# S202D.net
KiCad netlist of a schematic drawn in EAGLE
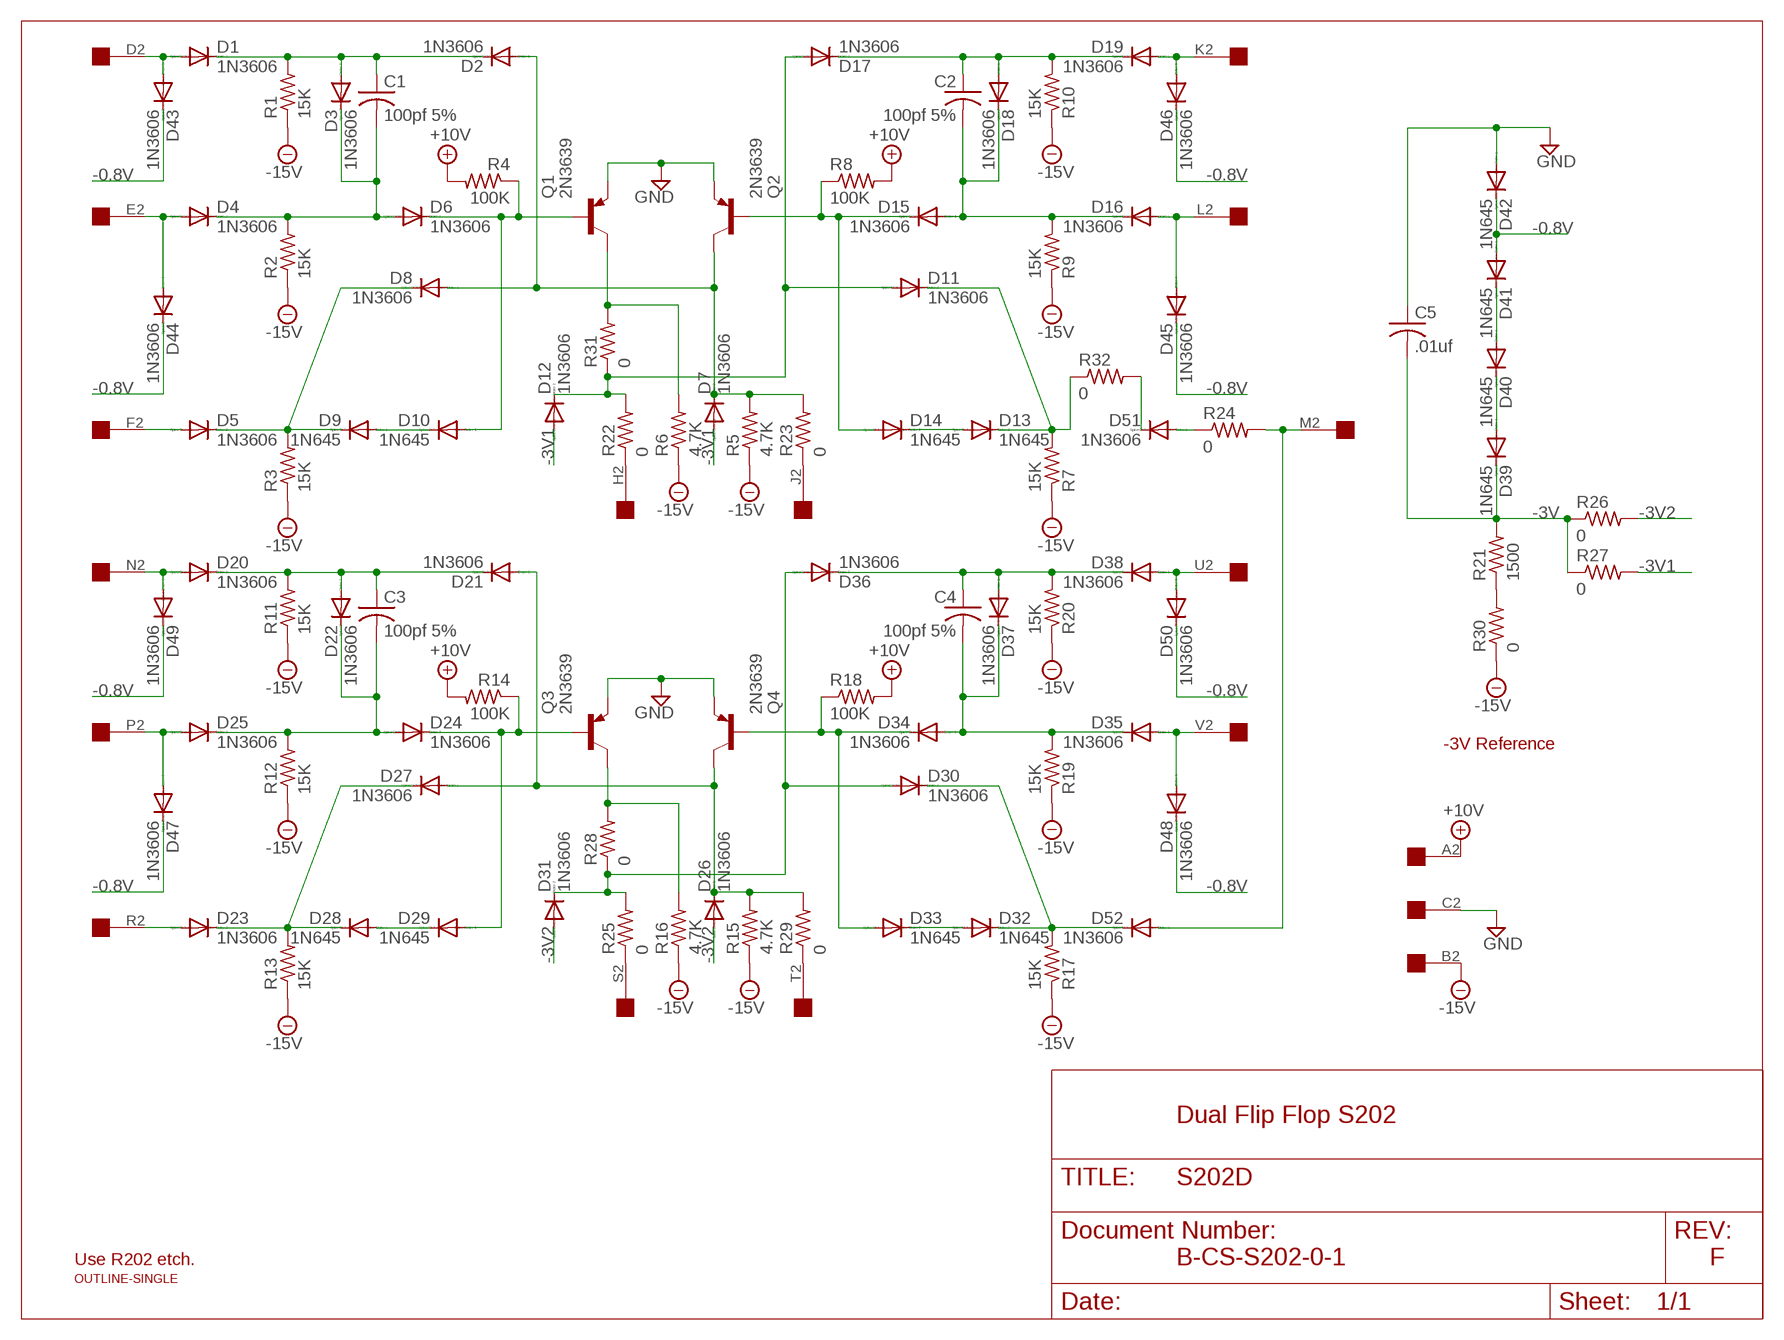
[diagram p0: schematic, sheet 1]

(export (version "E")
  (design (tool "Eeschema 10.0.6"))
  (components
    (comp (ref "C1")
      (value "100pf 5%")
      (footprint "eagle-import:C050-025X075")
      (libsource (lib "eagle-import") (part "C-US050-025X075"))
    )
    (comp (ref "C2")
      (value "100pf 5%")
      (footprint "eagle-import:C050-025X075")
      (libsource (lib "eagle-import") (part "C-US050-025X075"))
    )
    (comp (ref "C3")
      (value "100pf 5%")
      (footprint "eagle-import:C050-025X075")
      (libsource (lib "eagle-import") (part "C-US050-025X075"))
    )
    (comp (ref "C4")
      (value "100pf 5%")
      (footprint "eagle-import:C050-025X075")
      (libsource (lib "eagle-import") (part "C-US050-025X075"))
    )
    (comp (ref "C5")
      (value ".01uf")
      (footprint "eagle-import:C050-025X075")
      (libsource (lib "eagle-import") (part "C-US050-025X075"))
    )
    (comp (ref "D1")
      (value "1N3606")
      (footprint "eagle-import:DO35-10")
      (libsource (lib "eagle-import") (part "1N4148DO35-10"))
    )
    (comp (ref "D2")
      (value "1N3606")
      (footprint "eagle-import:DO35-10")
      (libsource (lib "eagle-import") (part "1N4148DO35-10"))
    )
    (comp (ref "D3")
      (value "1N3606")
      (footprint "eagle-import:DO35-10")
      (libsource (lib "eagle-import") (part "1N4148DO35-10"))
    )
    (comp (ref "D4")
      (value "1N3606")
      (footprint "eagle-import:DO35-10")
      (libsource (lib "eagle-import") (part "1N4148DO35-10"))
    )
    (comp (ref "D5")
      (value "1N3606")
      (footprint "eagle-import:DO35-10")
      (libsource (lib "eagle-import") (part "1N4148DO35-10"))
    )
    (comp (ref "D6")
      (value "1N3606")
      (footprint "eagle-import:DO35-10")
      (libsource (lib "eagle-import") (part "1N4148DO35-10"))
    )
    (comp (ref "D7")
      (value "1N3606")
      (footprint "eagle-import:DO35-10")
      (libsource (lib "eagle-import") (part "1N4148DO35-10"))
    )
    (comp (ref "D8")
      (value "1N3606")
      (footprint "eagle-import:DO35-10")
      (libsource (lib "eagle-import") (part "1N4148DO35-10"))
    )
    (comp (ref "D9")
      (value "1N645")
      (footprint "eagle-import:DO35-10")
      (libsource (lib "eagle-import") (part "1N4148DO35-10"))
    )
    (comp (ref "D10")
      (value "1N645")
      (footprint "eagle-import:DO35-10")
      (libsource (lib "eagle-import") (part "1N4148DO35-10"))
    )
    (comp (ref "D11")
      (value "1N3606")
      (footprint "eagle-import:DO35-10")
      (libsource (lib "eagle-import") (part "1N4148DO35-10"))
    )
    (comp (ref "D12")
      (value "1N3606")
      (footprint "eagle-import:DO35-10")
      (libsource (lib "eagle-import") (part "1N4148DO35-10"))
    )
    (comp (ref "D13")
      (value "1N645")
      (footprint "eagle-import:DO35-10")
      (libsource (lib "eagle-import") (part "1N4148DO35-10"))
    )
    (comp (ref "D14")
      (value "1N645")
      (footprint "eagle-import:DO35-10")
      (libsource (lib "eagle-import") (part "1N4148DO35-10"))
    )
    (comp (ref "D15")
      (value "1N3606")
      (footprint "eagle-import:DO35-10")
      (libsource (lib "eagle-import") (part "1N4148DO35-10"))
    )
    (comp (ref "D16")
      (value "1N3606")
      (footprint "eagle-import:DO35-10")
      (libsource (lib "eagle-import") (part "1N4148DO35-10"))
    )
    (comp (ref "D17")
      (value "1N3606")
      (footprint "eagle-import:DO35-10")
      (libsource (lib "eagle-import") (part "1N4148DO35-10"))
    )
    (comp (ref "D18")
      (value "1N3606")
      (footprint "eagle-import:DO35-10")
      (libsource (lib "eagle-import") (part "1N4148DO35-10"))
    )
    (comp (ref "D19")
      (value "1N3606")
      (footprint "eagle-import:DO35-10")
      (libsource (lib "eagle-import") (part "1N4148DO35-10"))
    )
    (comp (ref "D20")
      (value "1N3606")
      (footprint "eagle-import:DO35-10")
      (libsource (lib "eagle-import") (part "1N4148DO35-10"))
    )
    (comp (ref "D21")
      (value "1N3606")
      (footprint "eagle-import:DO35-10")
      (libsource (lib "eagle-import") (part "1N4148DO35-10"))
    )
    (comp (ref "D22")
      (value "1N3606")
      (footprint "eagle-import:DO35-10")
      (libsource (lib "eagle-import") (part "1N4148DO35-10"))
    )
    (comp (ref "D23")
      (value "1N3606")
      (footprint "eagle-import:DO35-10")
      (libsource (lib "eagle-import") (part "1N4148DO35-10"))
    )
    (comp (ref "D24")
      (value "1N3606")
      (footprint "eagle-import:DO35-10")
      (libsource (lib "eagle-import") (part "1N4148DO35-10"))
    )
    (comp (ref "D25")
      (value "1N3606")
      (footprint "eagle-import:DO35-10")
      (libsource (lib "eagle-import") (part "1N4148DO35-10"))
    )
    (comp (ref "D26")
      (value "1N3606")
      (footprint "eagle-import:DO35-10")
      (libsource (lib "eagle-import") (part "1N4148DO35-10"))
    )
    (comp (ref "D27")
      (value "1N3606")
      (footprint "eagle-import:DO35-10")
      (libsource (lib "eagle-import") (part "1N4148DO35-10"))
    )
    (comp (ref "D28")
      (value "1N645")
      (footprint "eagle-import:DO35-10")
      (libsource (lib "eagle-import") (part "1N4148DO35-10"))
    )
    (comp (ref "D29")
      (value "1N645")
      (footprint "eagle-import:DO35-10")
      (libsource (lib "eagle-import") (part "1N4148DO35-10"))
    )
    (comp (ref "D30")
      (value "1N3606")
      (footprint "eagle-import:DO35-10")
      (libsource (lib "eagle-import") (part "1N4148DO35-10"))
    )
    (comp (ref "D31")
      (value "1N3606")
      (footprint "eagle-import:DO35-10")
      (libsource (lib "eagle-import") (part "1N4148DO35-10"))
    )
    (comp (ref "D32")
      (value "1N645")
      (footprint "eagle-import:DO35-10")
      (libsource (lib "eagle-import") (part "1N4148DO35-10"))
    )
    (comp (ref "D33")
      (value "1N645")
      (footprint "eagle-import:DO35-10")
      (libsource (lib "eagle-import") (part "1N4148DO35-10"))
    )
    (comp (ref "D34")
      (value "1N3606")
      (footprint "eagle-import:DO35-10")
      (libsource (lib "eagle-import") (part "1N4148DO35-10"))
    )
    (comp (ref "D35")
      (value "1N3606")
      (footprint "eagle-import:DO35-10")
      (libsource (lib "eagle-import") (part "1N4148DO35-10"))
    )
    (comp (ref "D36")
      (value "1N3606")
      (footprint "eagle-import:DO35-10")
      (libsource (lib "eagle-import") (part "1N4148DO35-10"))
    )
    (comp (ref "D37")
      (value "1N3606")
      (footprint "eagle-import:DO35-10")
      (libsource (lib "eagle-import") (part "1N4148DO35-10"))
    )
    (comp (ref "D38")
      (value "1N3606")
      (footprint "eagle-import:DO35-10")
      (libsource (lib "eagle-import") (part "1N4148DO35-10"))
    )
    (comp (ref "D39")
      (value "1N645")
      (footprint "eagle-import:DO35-10")
      (libsource (lib "eagle-import") (part "1N4148DO35-10"))
    )
    (comp (ref "D40")
      (value "1N645")
      (footprint "eagle-import:DO35-10")
      (libsource (lib "eagle-import") (part "1N4148DO35-10"))
    )
    (comp (ref "D41")
      (value "1N645")
      (footprint "eagle-import:DO35-10")
      (libsource (lib "eagle-import") (part "1N4148DO35-10"))
    )
    (comp (ref "D42")
      (value "1N645")
      (footprint "eagle-import:DO35-10")
      (libsource (lib "eagle-import") (part "1N4148DO35-10"))
    )
    (comp (ref "D43")
      (value "1N3606")
      (footprint "eagle-import:DO35-10")
      (libsource (lib "eagle-import") (part "1N4148DO35-10"))
    )
    (comp (ref "D44")
      (value "1N3606")
      (footprint "eagle-import:DO35-10")
      (libsource (lib "eagle-import") (part "1N4148DO35-10"))
    )
    (comp (ref "D45")
      (value "1N3606")
      (footprint "eagle-import:DO35-10")
      (libsource (lib "eagle-import") (part "1N4148DO35-10"))
    )
    (comp (ref "D46")
      (value "1N3606")
      (footprint "eagle-import:DO35-10")
      (libsource (lib "eagle-import") (part "1N4148DO35-10"))
    )
    (comp (ref "D47")
      (value "1N3606")
      (footprint "eagle-import:DO35-10")
      (libsource (lib "eagle-import") (part "1N4148DO35-10"))
    )
    (comp (ref "D48")
      (value "1N3606")
      (footprint "eagle-import:DO35-10")
      (libsource (lib "eagle-import") (part "1N4148DO35-10"))
    )
    (comp (ref "D49")
      (value "1N3606")
      (footprint "eagle-import:DO35-10")
      (libsource (lib "eagle-import") (part "1N4148DO35-10"))
    )
    (comp (ref "D50")
      (value "1N3606")
      (footprint "eagle-import:DO35-10")
      (libsource (lib "eagle-import") (part "1N4148DO35-10"))
    )
    (comp (ref "D51")
      (value "1N3606")
      (footprint "eagle-import:DO35-10")
      (libsource (lib "eagle-import") (part "1N4148DO35-10"))
    )
    (comp (ref "D52")
      (value "1N3606")
      (footprint "eagle-import:DO35-10")
      (libsource (lib "eagle-import") (part "1N4148DO35-10"))
    )
    (comp (ref "Q1")
      (value "2N3639")
      (footprint "eagle-import:TO39")
      (libsource (lib "eagle-import") (part "2N3637"))
    )
    (comp (ref "Q2")
      (value "2N3639")
      (footprint "eagle-import:TO39")
      (libsource (lib "eagle-import") (part "2N3637"))
    )
    (comp (ref "Q3")
      (value "2N3639")
      (footprint "eagle-import:TO39")
      (libsource (lib "eagle-import") (part "2N3637"))
    )
    (comp (ref "Q4")
      (value "2N3639")
      (footprint "eagle-import:TO39")
      (libsource (lib "eagle-import") (part "2N3637"))
    )
    (comp (ref "R1")
      (value "15K")
      (footprint "eagle-import:0207_10")
      (libsource (lib "eagle-import") (part "R-US_0207/10"))
    )
    (comp (ref "R2")
      (value "15K")
      (footprint "eagle-import:0207_10")
      (libsource (lib "eagle-import") (part "R-US_0207/10"))
    )
    (comp (ref "R3")
      (value "15K")
      (footprint "eagle-import:0207_10")
      (libsource (lib "eagle-import") (part "R-US_0207/10"))
    )
    (comp (ref "R4")
      (value "100K")
      (footprint "eagle-import:0207_10")
      (libsource (lib "eagle-import") (part "R-US_0207/10"))
    )
    (comp (ref "R5")
      (value "4.7K")
      (footprint "eagle-import:0207_10")
      (libsource (lib "eagle-import") (part "R-US_0207/10"))
    )
    (comp (ref "R6")
      (value "4.7K")
      (footprint "eagle-import:0207_10")
      (libsource (lib "eagle-import") (part "R-US_0207/10"))
    )
    (comp (ref "R7")
      (value "15K")
      (footprint "eagle-import:0207_10")
      (libsource (lib "eagle-import") (part "R-US_0207/10"))
    )
    (comp (ref "R8")
      (value "100K")
      (footprint "eagle-import:0207_10")
      (libsource (lib "eagle-import") (part "R-US_0207/10"))
    )
    (comp (ref "R9")
      (value "15K")
      (footprint "eagle-import:0207_10")
      (libsource (lib "eagle-import") (part "R-US_0207/10"))
    )
    (comp (ref "R10")
      (value "15K")
      (footprint "eagle-import:0207_10")
      (libsource (lib "eagle-import") (part "R-US_0207/10"))
    )
    (comp (ref "R11")
      (value "15K")
      (footprint "eagle-import:0207_10")
      (libsource (lib "eagle-import") (part "R-US_0207/10"))
    )
    (comp (ref "R12")
      (value "15K")
      (footprint "eagle-import:0207_10")
      (libsource (lib "eagle-import") (part "R-US_0207/10"))
    )
    (comp (ref "R13")
      (value "15K")
      (footprint "eagle-import:0207_10")
      (libsource (lib "eagle-import") (part "R-US_0207/10"))
    )
    (comp (ref "R14")
      (value "100K")
      (footprint "eagle-import:0207_10")
      (libsource (lib "eagle-import") (part "R-US_0207/10"))
    )
    (comp (ref "R15")
      (value "4.7K")
      (footprint "eagle-import:0207_10")
      (libsource (lib "eagle-import") (part "R-US_0207/10"))
    )
    (comp (ref "R16")
      (value "4.7K")
      (footprint "eagle-import:0207_10")
      (libsource (lib "eagle-import") (part "R-US_0207/10"))
    )
    (comp (ref "R17")
      (value "15K")
      (footprint "eagle-import:0207_10")
      (libsource (lib "eagle-import") (part "R-US_0207/10"))
    )
    (comp (ref "R18")
      (value "100K")
      (footprint "eagle-import:0207_10")
      (libsource (lib "eagle-import") (part "R-US_0207/10"))
    )
    (comp (ref "R19")
      (value "15K")
      (footprint "eagle-import:0207_10")
      (libsource (lib "eagle-import") (part "R-US_0207/10"))
    )
    (comp (ref "R20")
      (value "15K")
      (footprint "eagle-import:0207_10")
      (libsource (lib "eagle-import") (part "R-US_0207/10"))
    )
    (comp (ref "R21")
      (value "1500")
      (footprint "eagle-import:0207_10")
      (libsource (lib "eagle-import") (part "R-US_0207/10"))
    )
    (comp (ref "R22")
      (value "0")
      (footprint "eagle-import:0207_10")
      (libsource (lib "eagle-import") (part "R-US_0207/10"))
    )
    (comp (ref "R23")
      (value "0")
      (footprint "eagle-import:0207_10")
      (libsource (lib "eagle-import") (part "R-US_0207/10"))
    )
    (comp (ref "R24")
      (value "0")
      (footprint "eagle-import:0207_10")
      (libsource (lib "eagle-import") (part "R-US_0207/10"))
    )
    (comp (ref "R25")
      (value "0")
      (footprint "eagle-import:0207_10")
      (libsource (lib "eagle-import") (part "R-US_0207/10"))
    )
    (comp (ref "R26")
      (value "0")
      (footprint "eagle-import:0207_10")
      (libsource (lib "eagle-import") (part "R-US_0207/10"))
    )
    (comp (ref "R27")
      (value "0")
      (footprint "eagle-import:0207_10")
      (libsource (lib "eagle-import") (part "R-US_0207/10"))
    )
    (comp (ref "R28")
      (value "0")
      (footprint "eagle-import:0207_10")
      (libsource (lib "eagle-import") (part "R-US_0207/10"))
    )
    (comp (ref "R29")
      (value "0")
      (footprint "eagle-import:0207_10")
      (libsource (lib "eagle-import") (part "R-US_0207/10"))
    )
    (comp (ref "R30")
      (value "0")
      (footprint "eagle-import:0207_10")
      (libsource (lib "eagle-import") (part "R-US_0207/10"))
    )
    (comp (ref "R31")
      (value "0")
      (footprint "eagle-import:0207_10")
      (libsource (lib "eagle-import") (part "R-US_0207/10"))
    )
    (comp (ref "R32")
      (value "0")
      (footprint "eagle-import:0207_10")
      (libsource (lib "eagle-import") (part "R-US_0207/10"))
    )
    (comp (ref "U$1")
      (value "OUTLINE-SINGLE")
      (footprint "eagle-import:SINGLE")
      (libsource (lib "eagle-import") (part "OUTLINE-SINGLE"))
    )
    (comp (ref "U$2")
      (value "EDGE-1")
      (footprint "eagle-import:EDGE-CON1")
      (libsource (lib "eagle-import") (part "EDGE-1"))
    )
  )
  (nets
    (net (code "1") (name "+10V") (class "Default")
      (node (ref "R14") (pin "2") (pinfunction "2_2") (pintype "passive"))
      (node (ref "R18") (pin "2") (pinfunction "2_2") (pintype "passive"))
      (node (ref "R4") (pin "2") (pinfunction "2_2") (pintype "passive"))
      (node (ref "R8") (pin "2") (pinfunction "2_2") (pintype "passive"))
      (node (ref "U$2") (pin "A2") (pinfunction "1_A2") (pintype "bidirectional"))
    )
    (net (code "2") (name "-15V") (class "Default")
      (node (ref "R1") (pin "1") (pinfunction "1_1") (pintype "passive"))
      (node (ref "R10") (pin "1") (pinfunction "1_1") (pintype "passive"))
      (node (ref "R11") (pin "1") (pinfunction "1_1") (pintype "passive"))
      (node (ref "R12") (pin "1") (pinfunction "1_1") (pintype "passive"))
      (node (ref "R13") (pin "1") (pinfunction "1_1") (pintype "passive"))
      (node (ref "R15") (pin "1") (pinfunction "1_1") (pintype "passive"))
      (node (ref "R16") (pin "1") (pinfunction "1_1") (pintype "passive"))
      (node (ref "R17") (pin "1") (pinfunction "1_1") (pintype "passive"))
      (node (ref "R19") (pin "1") (pinfunction "1_1") (pintype "passive"))
      (node (ref "R2") (pin "1") (pinfunction "1_1") (pintype "passive"))
      (node (ref "R20") (pin "1") (pinfunction "1_1") (pintype "passive"))
      (node (ref "R3") (pin "1") (pinfunction "1_1") (pintype "passive"))
      (node (ref "R30") (pin "1") (pinfunction "1_1") (pintype "passive"))
      (node (ref "R5") (pin "1") (pinfunction "1_1") (pintype "passive"))
      (node (ref "R6") (pin "1") (pinfunction "1_1") (pintype "passive"))
      (node (ref "R7") (pin "1") (pinfunction "1_1") (pintype "passive"))
      (node (ref "R9") (pin "1") (pinfunction "1_1") (pintype "passive"))
      (node (ref "U$2") (pin "B2") (pinfunction "1_B2") (pintype "bidirectional"))
    )
    (net (code "3") (name "/-0.8V") (class "Default")
      (node (ref "D41") (pin "A") (pinfunction "A_A") (pintype "passive"))
      (node (ref "D42") (pin "C") (pinfunction "C_C") (pintype "passive"))
      (node (ref "D43") (pin "C") (pinfunction "C_C") (pintype "passive"))
      (node (ref "D44") (pin "C") (pinfunction "C_C") (pintype "passive"))
      (node (ref "D45") (pin "C") (pinfunction "C_C") (pintype "passive"))
      (node (ref "D46") (pin "C") (pinfunction "C_C") (pintype "passive"))
      (node (ref "D47") (pin "C") (pinfunction "C_C") (pintype "passive"))
      (node (ref "D48") (pin "C") (pinfunction "C_C") (pintype "passive"))
      (node (ref "D49") (pin "C") (pinfunction "C_C") (pintype "passive"))
      (node (ref "D50") (pin "C") (pinfunction "C_C") (pintype "passive"))
    )
    (net (code "4") (name "/-3V") (class "Default")
      (node (ref "C5") (pin "2") (pinfunction "2_2") (pintype "passive"))
      (node (ref "D39") (pin "C") (pinfunction "C_C") (pintype "passive"))
      (node (ref "R21") (pin "2") (pinfunction "2_2") (pintype "passive"))
      (node (ref "R26") (pin "1") (pinfunction "1_1") (pintype "passive"))
      (node (ref "R27") (pin "1") (pinfunction "1_1") (pintype "passive"))
    )
    (net (code "5") (name "/-3V1") (class "Default")
      (node (ref "D12") (pin "A") (pinfunction "A_A") (pintype "passive"))
      (node (ref "D7") (pin "A") (pinfunction "A_A") (pintype "passive"))
      (node (ref "R27") (pin "2") (pinfunction "2_2") (pintype "passive"))
    )
    (net (code "6") (name "/-3V2") (class "Default")
      (node (ref "D26") (pin "A") (pinfunction "A_A") (pintype "passive"))
      (node (ref "D31") (pin "A") (pinfunction "A_A") (pintype "passive"))
      (node (ref "R26") (pin "2") (pinfunction "2_2") (pintype "passive"))
    )
    (net (code "7") (name "GND") (class "Default")
      (node (ref "C5") (pin "1") (pinfunction "1_1") (pintype "passive"))
      (node (ref "D42") (pin "A") (pinfunction "A_A") (pintype "passive"))
      (node (ref "Q1") (pin "1") (pinfunction "E_1") (pintype "passive"))
      (node (ref "Q2") (pin "1") (pinfunction "E_1") (pintype "passive"))
      (node (ref "Q3") (pin "1") (pinfunction "E_1") (pintype "passive"))
      (node (ref "Q4") (pin "1") (pinfunction "E_1") (pintype "passive"))
      (node (ref "U$2") (pin "C2") (pinfunction "1_C2") (pintype "bidirectional"))
    )
    (net (code "8") (name "Net-(C1-Pad1)") (class "Default")
      (node (ref "C1") (pin "1") (pinfunction "1_1") (pintype "passive"))
      (node (ref "D1") (pin "C") (pinfunction "C_C") (pintype "passive"))
      (node (ref "D2") (pin "C") (pinfunction "C_C") (pintype "passive"))
      (node (ref "D3") (pin "A") (pinfunction "A_A") (pintype "passive"))
      (node (ref "R1") (pin "2") (pinfunction "2_2") (pintype "passive"))
    )
    (net (code "9") (name "Net-(C1-Pad2)") (class "Default")
      (node (ref "C1") (pin "2") (pinfunction "2_2") (pintype "passive"))
      (node (ref "D3") (pin "C") (pinfunction "C_C") (pintype "passive"))
      (node (ref "D4") (pin "C") (pinfunction "C_C") (pintype "passive"))
      (node (ref "D6") (pin "A") (pinfunction "A_A") (pintype "passive"))
      (node (ref "R2") (pin "2") (pinfunction "2_2") (pintype "passive"))
    )
    (net (code "10") (name "Net-(C2-Pad1)") (class "Default")
      (node (ref "C2") (pin "1") (pinfunction "1_1") (pintype "passive"))
      (node (ref "D17") (pin "C") (pinfunction "C_C") (pintype "passive"))
      (node (ref "D18") (pin "A") (pinfunction "A_A") (pintype "passive"))
      (node (ref "D19") (pin "C") (pinfunction "C_C") (pintype "passive"))
      (node (ref "R10") (pin "2") (pinfunction "2_2") (pintype "passive"))
    )
    (net (code "11") (name "Net-(C2-Pad2)") (class "Default")
      (node (ref "C2") (pin "2") (pinfunction "2_2") (pintype "passive"))
      (node (ref "D15") (pin "A") (pinfunction "A_A") (pintype "passive"))
      (node (ref "D16") (pin "C") (pinfunction "C_C") (pintype "passive"))
      (node (ref "D18") (pin "C") (pinfunction "C_C") (pintype "passive"))
      (node (ref "R9") (pin "2") (pinfunction "2_2") (pintype "passive"))
    )
    (net (code "12") (name "Net-(C3-Pad1)") (class "Default")
      (node (ref "C3") (pin "1") (pinfunction "1_1") (pintype "passive"))
      (node (ref "D20") (pin "C") (pinfunction "C_C") (pintype "passive"))
      (node (ref "D21") (pin "C") (pinfunction "C_C") (pintype "passive"))
      (node (ref "D22") (pin "A") (pinfunction "A_A") (pintype "passive"))
      (node (ref "R11") (pin "2") (pinfunction "2_2") (pintype "passive"))
    )
    (net (code "13") (name "Net-(C3-Pad2)") (class "Default")
      (node (ref "C3") (pin "2") (pinfunction "2_2") (pintype "passive"))
      (node (ref "D22") (pin "C") (pinfunction "C_C") (pintype "passive"))
      (node (ref "D24") (pin "A") (pinfunction "A_A") (pintype "passive"))
      (node (ref "D25") (pin "C") (pinfunction "C_C") (pintype "passive"))
      (node (ref "R12") (pin "2") (pinfunction "2_2") (pintype "passive"))
    )
    (net (code "14") (name "Net-(C4-Pad1)") (class "Default")
      (node (ref "C4") (pin "1") (pinfunction "1_1") (pintype "passive"))
      (node (ref "D36") (pin "C") (pinfunction "C_C") (pintype "passive"))
      (node (ref "D37") (pin "A") (pinfunction "A_A") (pintype "passive"))
      (node (ref "D38") (pin "C") (pinfunction "C_C") (pintype "passive"))
      (node (ref "R20") (pin "2") (pinfunction "2_2") (pintype "passive"))
    )
    (net (code "15") (name "Net-(C4-Pad2)") (class "Default")
      (node (ref "C4") (pin "2") (pinfunction "2_2") (pintype "passive"))
      (node (ref "D34") (pin "A") (pinfunction "A_A") (pintype "passive"))
      (node (ref "D35") (pin "C") (pinfunction "C_C") (pintype "passive"))
      (node (ref "D37") (pin "C") (pinfunction "C_C") (pintype "passive"))
      (node (ref "R19") (pin "2") (pinfunction "2_2") (pintype "passive"))
    )
    (net (code "16") (name "Net-(D5-PadC)") (class "Default")
      (node (ref "D5") (pin "C") (pinfunction "C_C") (pintype "passive"))
      (node (ref "D8") (pin "C") (pinfunction "C_C") (pintype "passive"))
      (node (ref "D9") (pin "C") (pinfunction "C_C") (pintype "passive"))
      (node (ref "R3") (pin "2") (pinfunction "2_2") (pintype "passive"))
    )
    (net (code "17") (name "Net-(D10-PadC)") (class "Default")
      (node (ref "D10") (pin "C") (pinfunction "C_C") (pintype "passive"))
      (node (ref "D9") (pin "A") (pinfunction "A_A") (pintype "passive"))
    )
    (net (code "18") (name "Net-(D11-PadA)") (class "Default")
      (node (ref "D11") (pin "A") (pinfunction "A_A") (pintype "passive"))
      (node (ref "D12") (pin "C") (pinfunction "C_C") (pintype "passive"))
      (node (ref "D17") (pin "A") (pinfunction "A_A") (pintype "passive"))
      (node (ref "R22") (pin "2") (pinfunction "2_2") (pintype "passive"))
      (node (ref "R31") (pin "1") (pinfunction "1_1") (pintype "passive"))
    )
    (net (code "19") (name "Net-(D11-PadC)") (class "Default")
      (node (ref "D11") (pin "C") (pinfunction "C_C") (pintype "passive"))
      (node (ref "D13") (pin "C") (pinfunction "C_C") (pintype "passive"))
      (node (ref "R32") (pin "1") (pinfunction "1_1") (pintype "passive"))
      (node (ref "R7") (pin "2") (pinfunction "2_2") (pintype "passive"))
    )
    (net (code "20") (name "Net-(D13-PadA)") (class "Default")
      (node (ref "D13") (pin "A") (pinfunction "A_A") (pintype "passive"))
      (node (ref "D14") (pin "C") (pinfunction "C_C") (pintype "passive"))
    )
    (net (code "21") (name "Net-(D23-PadC)") (class "Default")
      (node (ref "D23") (pin "C") (pinfunction "C_C") (pintype "passive"))
      (node (ref "D27") (pin "C") (pinfunction "C_C") (pintype "passive"))
      (node (ref "D28") (pin "C") (pinfunction "C_C") (pintype "passive"))
      (node (ref "R13") (pin "2") (pinfunction "2_2") (pintype "passive"))
    )
    (net (code "22") (name "Net-(D28-PadA)") (class "Default")
      (node (ref "D28") (pin "A") (pinfunction "A_A") (pintype "passive"))
      (node (ref "D29") (pin "C") (pinfunction "C_C") (pintype "passive"))
    )
    (net (code "23") (name "Net-(D30-PadA)") (class "Default")
      (node (ref "D30") (pin "A") (pinfunction "A_A") (pintype "passive"))
      (node (ref "D31") (pin "C") (pinfunction "C_C") (pintype "passive"))
      (node (ref "D36") (pin "A") (pinfunction "A_A") (pintype "passive"))
      (node (ref "R25") (pin "2") (pinfunction "2_2") (pintype "passive"))
      (node (ref "R28") (pin "1") (pinfunction "1_1") (pintype "passive"))
    )
    (net (code "24") (name "Net-(D30-PadC)") (class "Default")
      (node (ref "D30") (pin "C") (pinfunction "C_C") (pintype "passive"))
      (node (ref "D32") (pin "C") (pinfunction "C_C") (pintype "passive"))
      (node (ref "D52") (pin "C") (pinfunction "C_C") (pintype "passive"))
      (node (ref "R17") (pin "2") (pinfunction "2_2") (pintype "passive"))
    )
    (net (code "25") (name "Net-(D32-PadA)") (class "Default")
      (node (ref "D32") (pin "A") (pinfunction "A_A") (pintype "passive"))
      (node (ref "D33") (pin "C") (pinfunction "C_C") (pintype "passive"))
    )
    (net (code "26") (name "Net-(D39-PadA)") (class "Default")
      (node (ref "D39") (pin "A") (pinfunction "A_A") (pintype "passive"))
      (node (ref "D40") (pin "C") (pinfunction "C_C") (pintype "passive"))
    )
    (net (code "27") (name "Net-(D40-PadA)") (class "Default")
      (node (ref "D40") (pin "A") (pinfunction "A_A") (pintype "passive"))
      (node (ref "D41") (pin "C") (pinfunction "C_C") (pintype "passive"))
    )
    (net (code "28") (name "Net-(D51-PadA)") (class "Default")
      (node (ref "D51") (pin "A") (pinfunction "A_A") (pintype "passive"))
      (node (ref "R24") (pin "1") (pinfunction "1_1") (pintype "passive"))
    )
    (net (code "29") (name "Net-(D51-PadC)") (class "Default")
      (node (ref "D51") (pin "C") (pinfunction "C_C") (pintype "passive"))
      (node (ref "R32") (pin "2") (pinfunction "2_2") (pintype "passive"))
    )
    (net (code "30") (name "Net-(Q1-B)") (class "Default")
      (node (ref "D10") (pin "A") (pinfunction "A_A") (pintype "passive"))
      (node (ref "D6") (pin "C") (pinfunction "C_C") (pintype "passive"))
      (node (ref "Q1") (pin "2") (pinfunction "B_2") (pintype "passive"))
      (node (ref "R4") (pin "1") (pinfunction "1_1") (pintype "passive"))
    )
    (net (code "31") (name "Net-(Q1-C)") (class "Default")
      (node (ref "Q1") (pin "3") (pinfunction "C_3") (pintype "passive"))
      (node (ref "R31") (pin "2") (pinfunction "2_2") (pintype "passive"))
      (node (ref "R6") (pin "2") (pinfunction "2_2") (pintype "passive"))
    )
    (net (code "32") (name "Net-(Q2-B)") (class "Default")
      (node (ref "D14") (pin "A") (pinfunction "A_A") (pintype "passive"))
      (node (ref "D15") (pin "C") (pinfunction "C_C") (pintype "passive"))
      (node (ref "Q2") (pin "2") (pinfunction "B_2") (pintype "passive"))
      (node (ref "R8") (pin "1") (pinfunction "1_1") (pintype "passive"))
    )
    (net (code "33") (name "Net-(Q2-C)") (class "Default")
      (node (ref "D2") (pin "A") (pinfunction "A_A") (pintype "passive"))
      (node (ref "D7") (pin "C") (pinfunction "C_C") (pintype "passive"))
      (node (ref "D8") (pin "A") (pinfunction "A_A") (pintype "passive"))
      (node (ref "Q2") (pin "3") (pinfunction "C_3") (pintype "passive"))
      (node (ref "R23") (pin "2") (pinfunction "2_2") (pintype "passive"))
      (node (ref "R5") (pin "2") (pinfunction "2_2") (pintype "passive"))
    )
    (net (code "34") (name "Net-(Q3-B)") (class "Default")
      (node (ref "D24") (pin "C") (pinfunction "C_C") (pintype "passive"))
      (node (ref "D29") (pin "A") (pinfunction "A_A") (pintype "passive"))
      (node (ref "Q3") (pin "2") (pinfunction "B_2") (pintype "passive"))
      (node (ref "R14") (pin "1") (pinfunction "1_1") (pintype "passive"))
    )
    (net (code "35") (name "Net-(Q3-C)") (class "Default")
      (node (ref "Q3") (pin "3") (pinfunction "C_3") (pintype "passive"))
      (node (ref "R16") (pin "2") (pinfunction "2_2") (pintype "passive"))
      (node (ref "R28") (pin "2") (pinfunction "2_2") (pintype "passive"))
    )
    (net (code "36") (name "Net-(Q4-B)") (class "Default")
      (node (ref "D33") (pin "A") (pinfunction "A_A") (pintype "passive"))
      (node (ref "D34") (pin "C") (pinfunction "C_C") (pintype "passive"))
      (node (ref "Q4") (pin "2") (pinfunction "B_2") (pintype "passive"))
      (node (ref "R18") (pin "1") (pinfunction "1_1") (pintype "passive"))
    )
    (net (code "37") (name "Net-(Q4-C)") (class "Default")
      (node (ref "D21") (pin "A") (pinfunction "A_A") (pintype "passive"))
      (node (ref "D26") (pin "C") (pinfunction "C_C") (pintype "passive"))
      (node (ref "D27") (pin "A") (pinfunction "A_A") (pintype "passive"))
      (node (ref "Q4") (pin "3") (pinfunction "C_3") (pintype "passive"))
      (node (ref "R15") (pin "2") (pinfunction "2_2") (pintype "passive"))
      (node (ref "R29") (pin "2") (pinfunction "2_2") (pintype "passive"))
    )
    (net (code "38") (name "Net-(R21-Pad1)") (class "Default")
      (node (ref "R21") (pin "1") (pinfunction "1_1") (pintype "passive"))
      (node (ref "R30") (pin "2") (pinfunction "2_2") (pintype "passive"))
    )
    (net (code "39") (name "Net-(U$2D-1)") (class "Default")
      (node (ref "D1") (pin "A") (pinfunction "A_A") (pintype "passive"))
      (node (ref "D43") (pin "A") (pinfunction "A_A") (pintype "passive"))
      (node (ref "U$2") (pin "D2") (pinfunction "1_D2") (pintype "bidirectional"))
    )
    (net (code "40") (name "Net-(U$2E-1)") (class "Default")
      (node (ref "D4") (pin "A") (pinfunction "A_A") (pintype "passive"))
      (node (ref "D44") (pin "A") (pinfunction "A_A") (pintype "passive"))
      (node (ref "U$2") (pin "E2") (pinfunction "1_E2") (pintype "bidirectional"))
    )
    (net (code "41") (name "Net-(U$2F-1)") (class "Default")
      (node (ref "D5") (pin "A") (pinfunction "A_A") (pintype "passive"))
      (node (ref "U$2") (pin "F2") (pinfunction "1_F2") (pintype "bidirectional"))
    )
    (net (code "42") (name "Net-(U$2G-1)") (class "Default")
      (node (ref "R22") (pin "1") (pinfunction "1_1") (pintype "passive"))
      (node (ref "U$2") (pin "H2") (pinfunction "1_H2") (pintype "bidirectional"))
    )
    (net (code "43") (name "Net-(U$2H-1)") (class "Default")
      (node (ref "R23") (pin "1") (pinfunction "1_1") (pintype "passive"))
      (node (ref "U$2") (pin "J2") (pinfunction "1_J2") (pintype "bidirectional"))
    )
    (net (code "44") (name "Net-(U$2I-1)") (class "Default")
      (node (ref "D19") (pin "A") (pinfunction "A_A") (pintype "passive"))
      (node (ref "D46") (pin "A") (pinfunction "A_A") (pintype "passive"))
      (node (ref "U$2") (pin "K2") (pinfunction "1_K2") (pintype "bidirectional"))
    )
    (net (code "45") (name "Net-(U$2J-1)") (class "Default")
      (node (ref "D16") (pin "A") (pinfunction "A_A") (pintype "passive"))
      (node (ref "D45") (pin "A") (pinfunction "A_A") (pintype "passive"))
      (node (ref "U$2") (pin "L2") (pinfunction "1_L2") (pintype "bidirectional"))
    )
    (net (code "46") (name "Net-(U$2K-1)") (class "Default")
      (node (ref "D52") (pin "A") (pinfunction "A_A") (pintype "passive"))
      (node (ref "R24") (pin "2") (pinfunction "2_2") (pintype "passive"))
      (node (ref "U$2") (pin "M2") (pinfunction "1_M2") (pintype "bidirectional"))
    )
    (net (code "47") (name "Net-(U$2L-1)") (class "Default")
      (node (ref "D20") (pin "A") (pinfunction "A_A") (pintype "passive"))
      (node (ref "D49") (pin "A") (pinfunction "A_A") (pintype "passive"))
      (node (ref "U$2") (pin "N2") (pinfunction "1_N2") (pintype "bidirectional"))
    )
    (net (code "48") (name "Net-(U$2M-1)") (class "Default")
      (node (ref "D25") (pin "A") (pinfunction "A_A") (pintype "passive"))
      (node (ref "D47") (pin "A") (pinfunction "A_A") (pintype "passive"))
      (node (ref "U$2") (pin "P2") (pinfunction "1_P2") (pintype "bidirectional"))
    )
    (net (code "49") (name "Net-(U$2N-1)") (class "Default")
      (node (ref "D23") (pin "A") (pinfunction "A_A") (pintype "passive"))
      (node (ref "U$2") (pin "R2") (pinfunction "1_R2") (pintype "bidirectional"))
    )
    (net (code "50") (name "Net-(U$2O-1)") (class "Default")
      (node (ref "R25") (pin "1") (pinfunction "1_1") (pintype "passive"))
      (node (ref "U$2") (pin "S2") (pinfunction "1_S2") (pintype "bidirectional"))
    )
    (net (code "51") (name "Net-(U$2P-1)") (class "Default")
      (node (ref "R29") (pin "1") (pinfunction "1_1") (pintype "passive"))
      (node (ref "U$2") (pin "T2") (pinfunction "1_T2") (pintype "bidirectional"))
    )
    (net (code "52") (name "Net-(U$2Q-1)") (class "Default")
      (node (ref "D38") (pin "A") (pinfunction "A_A") (pintype "passive"))
      (node (ref "D50") (pin "A") (pinfunction "A_A") (pintype "passive"))
      (node (ref "U$2") (pin "U2") (pinfunction "1_U2") (pintype "bidirectional"))
    )
    (net (code "53") (name "Net-(U$2R-1)") (class "Default")
      (node (ref "D35") (pin "A") (pinfunction "A_A") (pintype "passive"))
      (node (ref "D48") (pin "A") (pinfunction "A_A") (pintype "passive"))
      (node (ref "U$2") (pin "V2") (pinfunction "1_V2") (pintype "bidirectional"))
    )
  )
)
